# minicopter.net
KiCad netlist of a schematic drawn in EAGLE
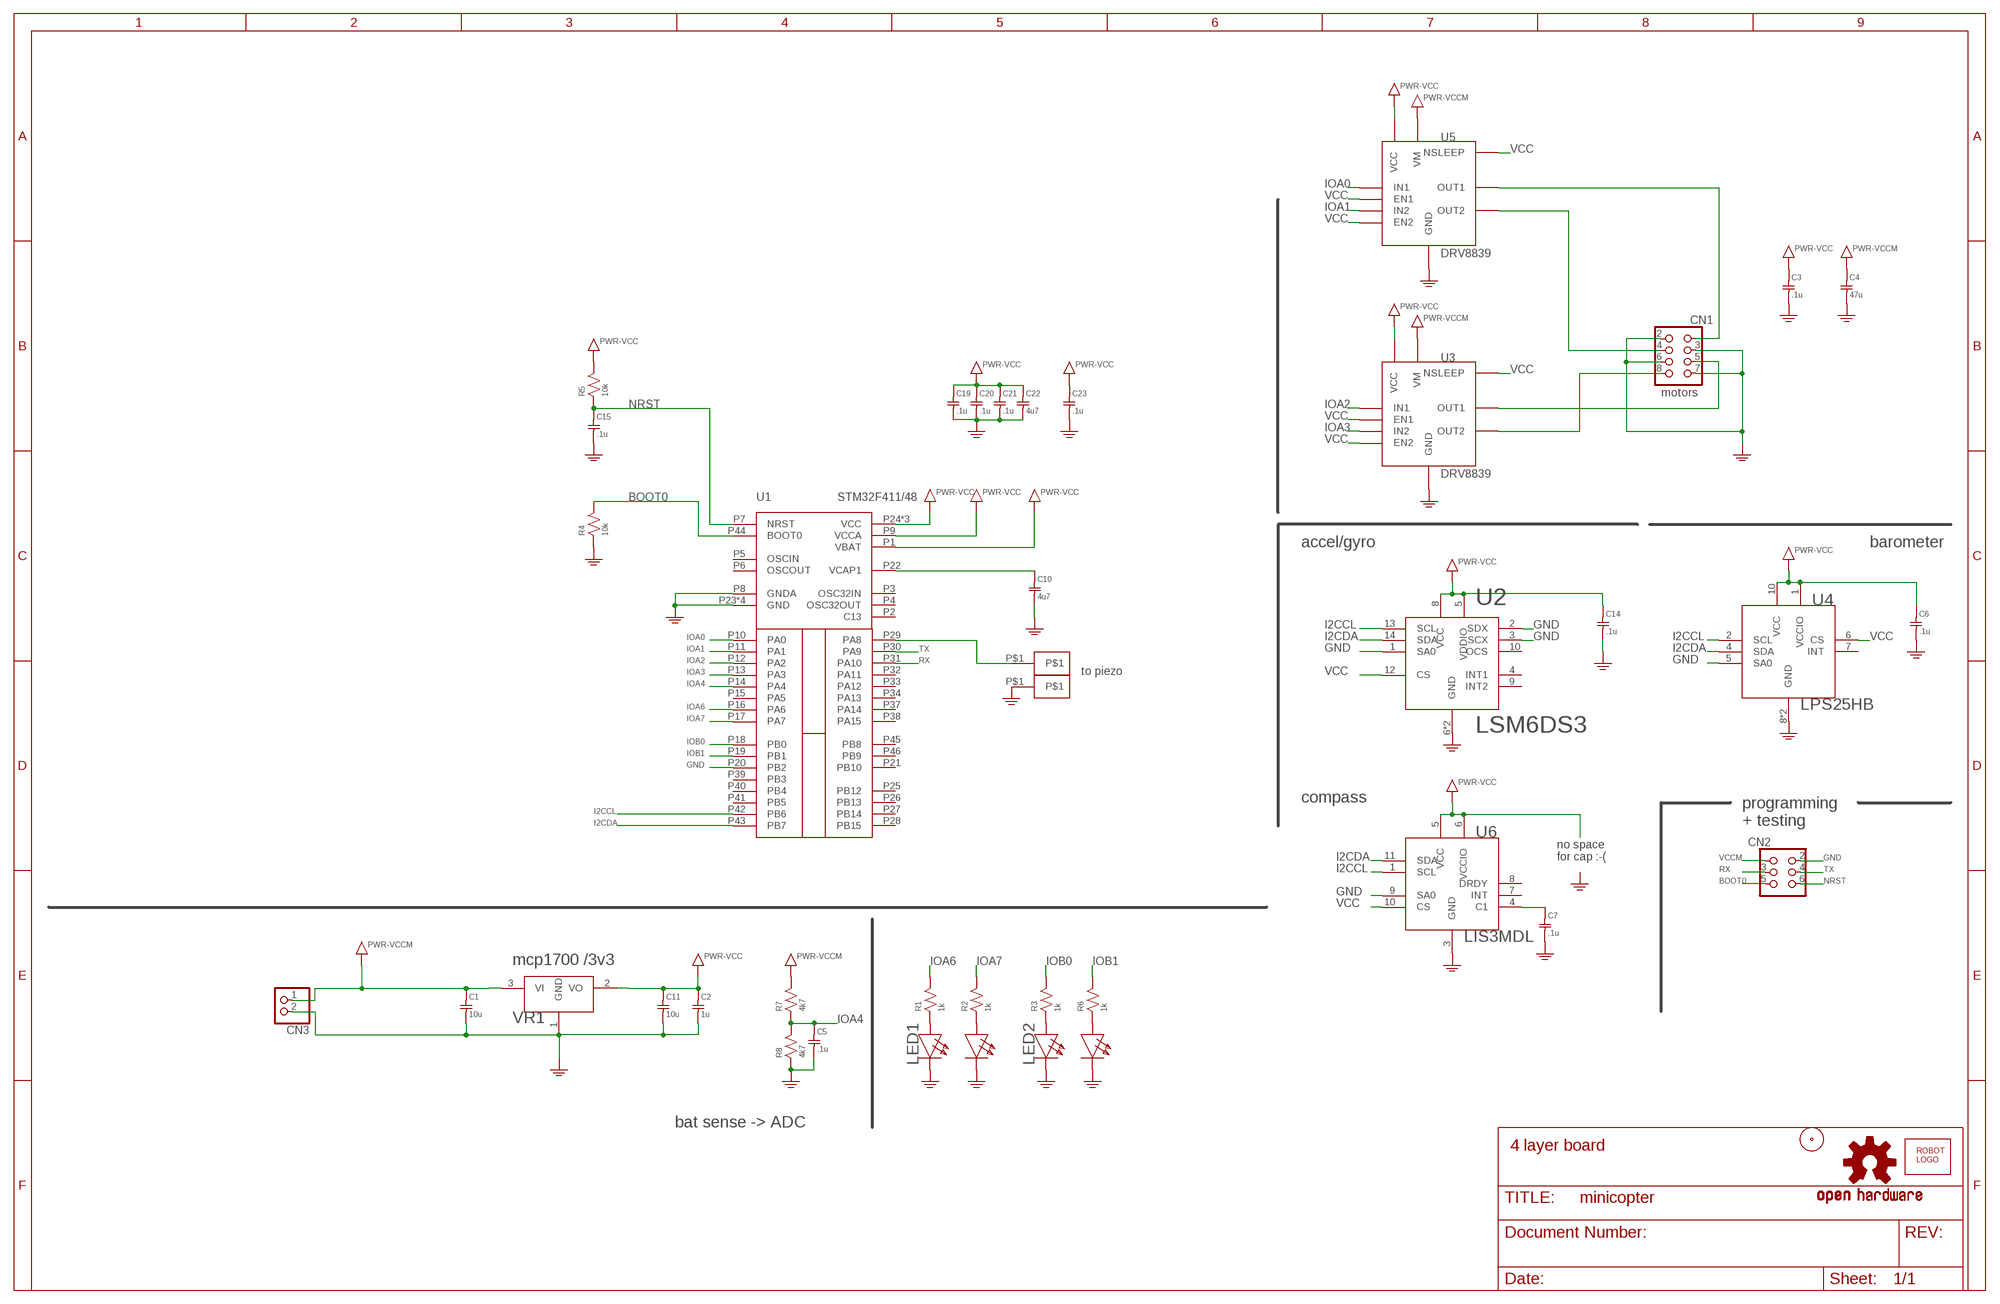
[diagram p0: schematic, sheet 1]

(export (version "E")
  (design (tool "Eeschema 10.0.6"))
  (components
    (comp (ref "C1")
      (value "10u")
      (footprint "eagle-import:SMD0603")
      (libsource (lib "eagle-import") (part "C0603"))
    )
    (comp (ref "C2")
      (value "1u")
      (footprint "eagle-import:SMD0603")
      (libsource (lib "eagle-import") (part "C0603"))
    )
    (comp (ref "C3")
      (value ".1u")
      (footprint "eagle-import:SMD0603")
      (libsource (lib "eagle-import") (part "C0603"))
    )
    (comp (ref "C4")
      (value "47u")
      (footprint "eagle-import:SMD0805")
      (libsource (lib "eagle-import") (part "C0805"))
    )
    (comp (ref "C5")
      (value ".1u")
      (footprint "eagle-import:SMD0603")
      (libsource (lib "eagle-import") (part "C0603"))
    )
    (comp (ref "C6")
      (value ".1u")
      (footprint "eagle-import:SMD0603")
      (libsource (lib "eagle-import") (part "C0603"))
    )
    (comp (ref "C7")
      (value ".1u")
      (footprint "eagle-import:SMD0603")
      (libsource (lib "eagle-import") (part "C0603"))
    )
    (comp (ref "C10")
      (value "4u7")
      (footprint "eagle-import:SMD0603")
      (libsource (lib "eagle-import") (part "C0603"))
    )
    (comp (ref "C11")
      (value "10u")
      (footprint "eagle-import:SMD0603")
      (libsource (lib "eagle-import") (part "C0603"))
    )
    (comp (ref "C14")
      (value ".1u")
      (footprint "eagle-import:SMD0603")
      (libsource (lib "eagle-import") (part "C0603"))
    )
    (comp (ref "C15")
      (value ".1u")
      (footprint "eagle-import:SMD0603")
      (libsource (lib "eagle-import") (part "C0603"))
    )
    (comp (ref "C19")
      (value ".1u")
      (footprint "eagle-import:SMD0603")
      (libsource (lib "eagle-import") (part "C0603"))
    )
    (comp (ref "C20")
      (value ".1u")
      (footprint "eagle-import:SMD0603")
      (libsource (lib "eagle-import") (part "C0603"))
    )
    (comp (ref "C21")
      (value ".1u")
      (footprint "eagle-import:SMD0603")
      (libsource (lib "eagle-import") (part "C0603"))
    )
    (comp (ref "C22")
      (value "4u7")
      (footprint "eagle-import:SMD0603")
      (libsource (lib "eagle-import") (part "C0603"))
    )
    (comp (ref "C23")
      (value ".1u")
      (footprint "eagle-import:SMD0603")
      (libsource (lib "eagle-import") (part "C0603"))
    )
    (comp (ref "CN1")
      (value "HEADER-2X4")
      (footprint "eagle-import:HEADER-2X04-THM")
      (libsource (lib "eagle-import") (part "HEADER-2X4"))
    )
    (comp (ref "CN2")
      (value "HEADER-3X2-PTH")
      (footprint "eagle-import:HEADER-3X2-PTH")
      (libsource (lib "eagle-import") (part "HEADER-3X2-PTH"))
    )
    (comp (ref "CN3")
      (value "JST_2PIN-THM")
      (footprint "eagle-import:JST-PH-2-THM")
      (libsource (lib "eagle-import") (part "JST_2PIN-THM"))
    )
    (comp (ref "CN4")
      (value "HEADER-1X1SMALL")
      (footprint "eagle-import:HEADER-1X1-SMALL")
      (libsource (lib "eagle-import") (part "HEADER-1X1SMALL"))
    )
    (comp (ref "CN5")
      (value "HEADER-1X1SMALL")
      (footprint "eagle-import:HEADER-1X1-SMALL")
      (libsource (lib "eagle-import") (part "HEADER-1X1SMALL"))
    )
    (comp (ref "LED1")
      (value "LED-DUAL0805")
      (footprint "eagle-import:SMD0805-DUAL")
      (libsource (lib "eagle-import") (part "LED-DUAL0805"))
    )
    (comp (ref "LED2")
      (value "LED-DUAL0805")
      (footprint "eagle-import:SMD0805-DUAL")
      (libsource (lib "eagle-import") (part "LED-DUAL0805"))
    )
    (comp (ref "LOGO1")
      (value "OSHW-LOGOM")
      (footprint "eagle-import:OSHW-LOGO-M")
      (libsource (lib "eagle-import") (part "OSHW-LOGOM"))
    )
    (comp (ref "R1")
      (value "1k")
      (footprint "eagle-import:SMD0603")
      (libsource (lib "eagle-import") (part "R0603"))
    )
    (comp (ref "R2")
      (value "1k")
      (footprint "eagle-import:SMD0603")
      (libsource (lib "eagle-import") (part "R0603"))
    )
    (comp (ref "R3")
      (value "1k")
      (footprint "eagle-import:SMD0603")
      (libsource (lib "eagle-import") (part "R0603"))
    )
    (comp (ref "R4")
      (value "10k")
      (footprint "eagle-import:SMD0603")
      (libsource (lib "eagle-import") (part "R0603"))
    )
    (comp (ref "R5")
      (value "10k")
      (footprint "eagle-import:SMD0603")
      (libsource (lib "eagle-import") (part "R0603"))
    )
    (comp (ref "R6")
      (value "1k")
      (footprint "eagle-import:SMD0603")
      (libsource (lib "eagle-import") (part "R0603"))
    )
    (comp (ref "R7")
      (value "4k7")
      (footprint "eagle-import:SMD0603")
      (libsource (lib "eagle-import") (part "R0603"))
    )
    (comp (ref "R8")
      (value "4k7")
      (footprint "eagle-import:SMD0603")
      (libsource (lib "eagle-import") (part "R0603"))
    )
    (comp (ref "U$1")
      (value "ROBOTMAN-LOGO")
      (footprint "eagle-import:ROBOTMAN-LOGO")
      (libsource (lib "eagle-import") (part "ROBOTMAN-LOGO"))
    )
    (comp (ref "U$2")
      (value "FIDUCIAL")
      (footprint "eagle-import:FIDUCIAL")
      (libsource (lib "eagle-import") (part "FIDUCIAL"))
    )
    (comp (ref "U1")
      (value "STM32F411/48")
      (footprint "eagle-import:UQPFN48")
      (libsource (lib "eagle-import") (part "STM32F411/48"))
    )
    (comp (ref "U2")
      (value "LSM6DS3")
      (footprint "eagle-import:LGA14A")
      (libsource (lib "eagle-import") (part "LSM6DS3"))
    )
    (comp (ref "U3")
      (value "DRV8839")
      (footprint "eagle-import:WSON12")
      (libsource (lib "eagle-import") (part "DRV8839"))
    )
    (comp (ref "U4")
      (value "LPS25HB")
      (footprint "eagle-import:HLGA10L")
      (libsource (lib "eagle-import") (part "LPS25HB"))
    )
    (comp (ref "U5")
      (value "DRV8839")
      (footprint "eagle-import:WSON12")
      (libsource (lib "eagle-import") (part "DRV8839"))
    )
    (comp (ref "U6")
      (value "LIS3MDL")
      (footprint "eagle-import:LGA12")
      (libsource (lib "eagle-import") (part "LIS3MDL"))
    )
    (comp (ref "VR1")
      (value "mcp1700 /3v3")
      (footprint "eagle-import:SOT-23-3")
      (libsource (lib "eagle-import") (part "REGULATOR-SOT23-3"))
    )
  )
  (nets
    (net (code "1") (name "/BOOT0") (class "Default")
      (node (ref "CN2") (pin "5") (pinfunction "P$5_5") (pintype "passive"))
      (node (ref "R4") (pin "2") (pinfunction "P$2_2") (pintype "passive"))
      (node (ref "U1") (pin "P44") (pinfunction "BOOT0_P44") (pintype "bidirectional"))
    )
    (net (code "2") (name "/I2CCL") (class "Default")
      (node (ref "U1") (pin "P42") (pinfunction "PB6_P42") (pintype "bidirectional"))
      (node (ref "U2") (pin "13") (pinfunction "SCL_13") (pintype "bidirectional"))
      (node (ref "U4") (pin "2") (pinfunction "SCL_2") (pintype "bidirectional"))
      (node (ref "U6") (pin "1") (pinfunction "SCL_1") (pintype "bidirectional"))
    )
    (net (code "3") (name "/I2CDA") (class "Default")
      (node (ref "U1") (pin "P43") (pinfunction "PB7_P43") (pintype "bidirectional"))
      (node (ref "U2") (pin "14") (pinfunction "SDA_14") (pintype "bidirectional"))
      (node (ref "U4") (pin "4") (pinfunction "SDA_4") (pintype "bidirectional"))
      (node (ref "U6") (pin "11") (pinfunction "SDA_11") (pintype "bidirectional"))
    )
    (net (code "4") (name "/IOA0") (class "Default")
      (node (ref "U1") (pin "P10") (pinfunction "PA0_P10") (pintype "bidirectional"))
      (node (ref "U5") (pin "10") (pinfunction "IN1_10") (pintype "input"))
    )
    (net (code "5") (name "/IOA1") (class "Default")
      (node (ref "U1") (pin "P11") (pinfunction "PA1_P11") (pintype "bidirectional"))
      (node (ref "U5") (pin "8") (pinfunction "IN2_8") (pintype "input"))
    )
    (net (code "6") (name "/IOA2") (class "Default")
      (node (ref "U1") (pin "P12") (pinfunction "PA2_P12") (pintype "bidirectional"))
      (node (ref "U3") (pin "10") (pinfunction "IN1_10") (pintype "input"))
    )
    (net (code "7") (name "/IOA3") (class "Default")
      (node (ref "U1") (pin "P13") (pinfunction "PA3_P13") (pintype "bidirectional"))
      (node (ref "U3") (pin "8") (pinfunction "IN2_8") (pintype "input"))
    )
    (net (code "8") (name "/IOA4") (class "Default")
      (node (ref "C5") (pin "1") (pinfunction "P$1_1") (pintype "passive"))
      (node (ref "R7") (pin "1") (pinfunction "P$1_1") (pintype "passive"))
      (node (ref "R8") (pin "2") (pinfunction "P$2_2") (pintype "passive"))
      (node (ref "U1") (pin "P14") (pinfunction "PA4_P14") (pintype "bidirectional"))
    )
    (net (code "9") (name "/IOA6") (class "Default")
      (node (ref "R1") (pin "2") (pinfunction "P$2_2") (pintype "passive"))
      (node (ref "U1") (pin "P16") (pinfunction "PA6_P16") (pintype "bidirectional"))
    )
    (net (code "10") (name "/IOA7") (class "Default")
      (node (ref "R2") (pin "2") (pinfunction "P$2_2") (pintype "passive"))
      (node (ref "U1") (pin "P17") (pinfunction "PA7_P17") (pintype "bidirectional"))
    )
    (net (code "11") (name "/IOB0") (class "Default")
      (node (ref "R3") (pin "2") (pinfunction "P$2_2") (pintype "passive"))
      (node (ref "U1") (pin "P18") (pinfunction "PB0_P18") (pintype "bidirectional"))
    )
    (net (code "12") (name "/IOB1") (class "Default")
      (node (ref "R6") (pin "2") (pinfunction "P$2_2") (pintype "passive"))
      (node (ref "U1") (pin "P19") (pinfunction "PB1_P19") (pintype "bidirectional"))
    )
    (net (code "13") (name "/NRST") (class "Default")
      (node (ref "C15") (pin "1") (pinfunction "P$1_1") (pintype "passive"))
      (node (ref "CN2") (pin "6") (pinfunction "P$6_6") (pintype "passive"))
      (node (ref "R5") (pin "1") (pinfunction "P$1_1") (pintype "passive"))
      (node (ref "U1") (pin "P7") (pinfunction "NRST_P7") (pintype "bidirectional"))
    )
    (net (code "14") (name "/RX") (class "Default")
      (node (ref "CN2") (pin "3") (pinfunction "P$3_3") (pintype "passive"))
      (node (ref "U1") (pin "P31") (pinfunction "PA10_P31") (pintype "bidirectional"))
    )
    (net (code "15") (name "/TX") (class "Default")
      (node (ref "CN2") (pin "4") (pinfunction "P$4_4") (pintype "passive"))
      (node (ref "U1") (pin "P30") (pinfunction "PA9_P30") (pintype "bidirectional"))
    )
    (net (code "16") (name "Net-(C7-P$1)") (class "Default")
      (node (ref "C7") (pin "1") (pinfunction "P$1_1") (pintype "passive"))
      (node (ref "U6") (pin "4") (pinfunction "C1_4") (pintype "bidirectional"))
    )
    (net (code "17") (name "Net-(C10-P$1)") (class "Default")
      (node (ref "C10") (pin "1") (pinfunction "P$1_1") (pintype "passive"))
      (node (ref "U1") (pin "P22") (pinfunction "VCAP1_P22") (pintype "bidirectional"))
    )
    (net (code "18") (name "Net-(CN1-P$1)") (class "Default")
      (node (ref "CN1") (pin "1") (pinfunction "P$1_1") (pintype "passive"))
      (node (ref "U5") (pin "3") (pinfunction "OUT1_3") (pintype "output"))
    )
    (net (code "19") (name "Net-(CN1-P$4)") (class "Default")
      (node (ref "CN1") (pin "4") (pinfunction "P$4_4") (pintype "passive"))
      (node (ref "U5") (pin "4") (pinfunction "OUT2_4") (pintype "output"))
    )
    (net (code "20") (name "Net-(CN1-P$5)") (class "Default")
      (node (ref "CN1") (pin "5") (pinfunction "P$5_5") (pintype "passive"))
      (node (ref "U3") (pin "3") (pinfunction "OUT1_3") (pintype "output"))
    )
    (net (code "21") (name "Net-(CN1-P$8)") (class "Default")
      (node (ref "CN1") (pin "8") (pinfunction "P$8_8") (pintype "passive"))
      (node (ref "U3") (pin "4") (pinfunction "OUT2_4") (pintype "output"))
    )
    (net (code "22") (name "Net-(LED1-AB)") (class "Default")
      (node (ref "LED1") (pin "1") (pinfunction "AB_1") (pintype "passive"))
      (node (ref "R1") (pin "1") (pinfunction "P$1_1") (pintype "passive"))
    )
    (net (code "23") (name "Net-(LED1-AR)") (class "Default")
      (node (ref "LED1") (pin "4") (pinfunction "AR_4") (pintype "passive"))
      (node (ref "R2") (pin "1") (pinfunction "P$1_1") (pintype "passive"))
    )
    (net (code "24") (name "Net-(LED2-AB)") (class "Default")
      (node (ref "LED2") (pin "1") (pinfunction "AB_1") (pintype "passive"))
      (node (ref "R3") (pin "1") (pinfunction "P$1_1") (pintype "passive"))
    )
    (net (code "25") (name "Net-(LED2-AR)") (class "Default")
      (node (ref "LED2") (pin "4") (pinfunction "AR_4") (pintype "passive"))
      (node (ref "R6") (pin "1") (pinfunction "P$1_1") (pintype "passive"))
    )
    (net (code "26") (name "Net-(U1-PA8)") (class "Default")
      (node (ref "CN4") (pin "P$1") (pinfunction "P$1_P$1") (pintype "bidirectional"))
      (node (ref "U1") (pin "P29") (pinfunction "PA8_P29") (pintype "bidirectional"))
    )
    (net (code "27") (name "PWR-GND") (class "Default")
      (node (ref "C1") (pin "2") (pinfunction "P$2_2") (pintype "passive"))
      (node (ref "C10") (pin "2") (pinfunction "P$2_2") (pintype "passive"))
      (node (ref "C11") (pin "2") (pinfunction "P$2_2") (pintype "passive"))
      (node (ref "C14") (pin "2") (pinfunction "P$2_2") (pintype "passive"))
      (node (ref "C15") (pin "2") (pinfunction "P$2_2") (pintype "passive"))
      (node (ref "C19") (pin "2") (pinfunction "P$2_2") (pintype "passive"))
      (node (ref "C2") (pin "2") (pinfunction "P$2_2") (pintype "passive"))
      (node (ref "C20") (pin "2") (pinfunction "P$2_2") (pintype "passive"))
      (node (ref "C21") (pin "2") (pinfunction "P$2_2") (pintype "passive"))
      (node (ref "C22") (pin "2") (pinfunction "P$2_2") (pintype "passive"))
      (node (ref "C23") (pin "2") (pinfunction "P$2_2") (pintype "passive"))
      (node (ref "C3") (pin "2") (pinfunction "P$2_2") (pintype "passive"))
      (node (ref "C4") (pin "2") (pinfunction "P$2_2") (pintype "passive"))
      (node (ref "C5") (pin "2") (pinfunction "P$2_2") (pintype "passive"))
      (node (ref "C6") (pin "2") (pinfunction "P$2_2") (pintype "passive"))
      (node (ref "C7") (pin "2") (pinfunction "P$2_2") (pintype "passive"))
      (node (ref "CN1") (pin "2") (pinfunction "P$2_2") (pintype "passive"))
      (node (ref "CN1") (pin "3") (pinfunction "P$3_3") (pintype "passive"))
      (node (ref "CN1") (pin "6") (pinfunction "P$6_6") (pintype "passive"))
      (node (ref "CN1") (pin "7") (pinfunction "P$7_7") (pintype "passive"))
      (node (ref "CN2") (pin "2") (pinfunction "P$2_2") (pintype "passive"))
      (node (ref "CN3") (pin "2") (pinfunction "1_2") (pintype "passive"))
      (node (ref "CN5") (pin "P$1") (pinfunction "P$1_P$1") (pintype "bidirectional"))
      (node (ref "LED1") (pin "2") (pinfunction "CB_2") (pintype "passive"))
      (node (ref "LED1") (pin "3") (pinfunction "CR_3") (pintype "passive"))
      (node (ref "LED2") (pin "2") (pinfunction "CB_2") (pintype "passive"))
      (node (ref "LED2") (pin "3") (pinfunction "CR_3") (pintype "passive"))
      (node (ref "R4") (pin "1") (pinfunction "P$1_1") (pintype "passive"))
      (node (ref "R8") (pin "1") (pinfunction "P$1_1") (pintype "passive"))
      (node (ref "U1") (pin "P20") (pinfunction "PB2_P20") (pintype "bidirectional"))
      (node (ref "U1") (pin "P23") (pinfunction "GND_P23") (pintype "bidirectional"))
      (node (ref "U1") (pin "P35") (pinfunction "GND_P35") (pintype "bidirectional"))
      (node (ref "U1") (pin "P47") (pinfunction "GND_P47") (pintype "bidirectional"))
      (node (ref "U1") (pin "P8") (pinfunction "GNDA_P8") (pintype "bidirectional"))
      (node (ref "U1") (pin "PAD") (pinfunction "GND_PAD") (pintype "bidirectional"))
      (node (ref "U2") (pin "1") (pinfunction "SA0_1") (pintype "bidirectional"))
      (node (ref "U2") (pin "2") (pinfunction "SDX_2") (pintype "bidirectional"))
      (node (ref "U2") (pin "3") (pinfunction "SCX_3") (pintype "bidirectional"))
      (node (ref "U2") (pin "6") (pinfunction "GND_6") (pintype "power_in"))
      (node (ref "U2") (pin "7") (pinfunction "GND_7") (pintype "power_in"))
      (node (ref "U3") (pin "5") (pinfunction "GND_5") (pintype "bidirectional"))
      (node (ref "U3") (pin "6") (pinfunction "GND_6") (pintype "bidirectional"))
      (node (ref "U3") (pin "GND3") (pinfunction "GND_GND3") (pintype "bidirectional"))
      (node (ref "U3") (pin "GND4") (pinfunction "GND_GND4") (pintype "bidirectional"))
      (node (ref "U3") (pin "GND5") (pinfunction "GND_GND5") (pintype "bidirectional"))
      (node (ref "U3") (pin "GND6") (pinfunction "GND_GND6") (pintype "bidirectional"))
      (node (ref "U3") (pin "GND7") (pinfunction "GND_GND7") (pintype "bidirectional"))
      (node (ref "U4") (pin "5") (pinfunction "SA0_5") (pintype "bidirectional"))
      (node (ref "U4") (pin "8") (pinfunction "GND_8") (pintype "bidirectional"))
      (node (ref "U4") (pin "9") (pinfunction "GND_9") (pintype "bidirectional"))
      (node (ref "U5") (pin "5") (pinfunction "GND_5") (pintype "bidirectional"))
      (node (ref "U5") (pin "6") (pinfunction "GND_6") (pintype "bidirectional"))
      (node (ref "U5") (pin "GND3") (pinfunction "GND_GND3") (pintype "bidirectional"))
      (node (ref "U5") (pin "GND4") (pinfunction "GND_GND4") (pintype "bidirectional"))
      (node (ref "U5") (pin "GND5") (pinfunction "GND_GND5") (pintype "bidirectional"))
      (node (ref "U5") (pin "GND6") (pinfunction "GND_GND6") (pintype "bidirectional"))
      (node (ref "U5") (pin "GND7") (pinfunction "GND_GND7") (pintype "bidirectional"))
      (node (ref "U6") (pin "3") (pinfunction "GND_3") (pintype "bidirectional"))
      (node (ref "U6") (pin "9") (pinfunction "SA0_9") (pintype "bidirectional"))
      (node (ref "VR1") (pin "1") (pinfunction "GND_1") (pintype "bidirectional"))
    )
    (net (code "28") (name "PWR-VCC") (class "Default")
      (node (ref "C11") (pin "1") (pinfunction "P$1_1") (pintype "passive"))
      (node (ref "C14") (pin "1") (pinfunction "P$1_1") (pintype "passive"))
      (node (ref "C19") (pin "1") (pinfunction "P$1_1") (pintype "passive"))
      (node (ref "C2") (pin "1") (pinfunction "P$1_1") (pintype "passive"))
      (node (ref "C20") (pin "1") (pinfunction "P$1_1") (pintype "passive"))
      (node (ref "C21") (pin "1") (pinfunction "P$1_1") (pintype "passive"))
      (node (ref "C22") (pin "1") (pinfunction "P$1_1") (pintype "passive"))
      (node (ref "C23") (pin "1") (pinfunction "P$1_1") (pintype "passive"))
      (node (ref "C3") (pin "1") (pinfunction "P$1_1") (pintype "passive"))
      (node (ref "C6") (pin "1") (pinfunction "P$1_1") (pintype "passive"))
      (node (ref "R5") (pin "2") (pinfunction "P$2_2") (pintype "passive"))
      (node (ref "U1") (pin "P1") (pinfunction "VBAT_P1") (pintype "bidirectional"))
      (node (ref "U1") (pin "P24") (pinfunction "VCC_P24") (pintype "bidirectional"))
      (node (ref "U1") (pin "P36") (pinfunction "VCC_P36") (pintype "bidirectional"))
      (node (ref "U1") (pin "P48") (pinfunction "VCC_P48") (pintype "bidirectional"))
      (node (ref "U1") (pin "P9") (pinfunction "VCCA_P9") (pintype "bidirectional"))
      (node (ref "U2") (pin "12") (pinfunction "CS_12") (pintype "bidirectional"))
      (node (ref "U2") (pin "5") (pinfunction "VDDIO_5") (pintype "bidirectional"))
      (node (ref "U2") (pin "8") (pinfunction "VCC_8") (pintype "power_in"))
      (node (ref "U3") (pin "11") (pinfunction "NSLEEP_11") (pintype "input"))
      (node (ref "U3") (pin "12") (pinfunction "VCC_12") (pintype "bidirectional"))
      (node (ref "U3") (pin "7") (pinfunction "EN2_7") (pintype "input"))
      (node (ref "U3") (pin "9") (pinfunction "EN1_9") (pintype "input"))
      (node (ref "U4") (pin "1") (pinfunction "VCCIO_1") (pintype "bidirectional"))
      (node (ref "U4") (pin "10") (pinfunction "VCC_10") (pintype "bidirectional"))
      (node (ref "U4") (pin "6") (pinfunction "CS_6") (pintype "bidirectional"))
      (node (ref "U5") (pin "11") (pinfunction "NSLEEP_11") (pintype "input"))
      (node (ref "U5") (pin "12") (pinfunction "VCC_12") (pintype "bidirectional"))
      (node (ref "U5") (pin "7") (pinfunction "EN2_7") (pintype "input"))
      (node (ref "U5") (pin "9") (pinfunction "EN1_9") (pintype "input"))
      (node (ref "U6") (pin "10") (pinfunction "CS_10") (pintype "bidirectional"))
      (node (ref "U6") (pin "5") (pinfunction "VCC_5") (pintype "bidirectional"))
      (node (ref "U6") (pin "6") (pinfunction "VCCIO_6") (pintype "bidirectional"))
      (node (ref "VR1") (pin "2") (pinfunction "VO_2") (pintype "bidirectional"))
    )
    (net (code "29") (name "PWR-VCCM") (class "Default")
      (node (ref "C1") (pin "1") (pinfunction "P$1_1") (pintype "passive"))
      (node (ref "C4") (pin "1") (pinfunction "P$1_1") (pintype "passive"))
      (node (ref "CN2") (pin "1") (pinfunction "P$1_1") (pintype "passive"))
      (node (ref "CN3") (pin "1") (pinfunction "2_1") (pintype "passive"))
      (node (ref "R7") (pin "2") (pinfunction "P$2_2") (pintype "passive"))
      (node (ref "U3") (pin "1") (pinfunction "VM_1") (pintype "bidirectional"))
      (node (ref "U3") (pin "2") (pinfunction "VM_2") (pintype "bidirectional"))
      (node (ref "U5") (pin "1") (pinfunction "VM_1") (pintype "bidirectional"))
      (node (ref "U5") (pin "2") (pinfunction "VM_2") (pintype "bidirectional"))
      (node (ref "VR1") (pin "3") (pinfunction "VI_3") (pintype "bidirectional"))
    )
    (net (code "30") (name "unconnected-(U1-C13-PadP2)") (class "Default")
      (node (ref "U1") (pin "P2") (pinfunction "C13_P2") (pintype "bidirectional"))
    )
    (net (code "31") (name "unconnected-(U1-OSC32IN-PadP3)") (class "Default")
      (node (ref "U1") (pin "P3") (pinfunction "OSC32IN_P3") (pintype "bidirectional"))
    )
    (net (code "32") (name "unconnected-(U1-OSC32OUT-PadP4)") (class "Default")
      (node (ref "U1") (pin "P4") (pinfunction "OSC32OUT_P4") (pintype "bidirectional"))
    )
    (net (code "33") (name "unconnected-(U1-OSCIN-PadP5)") (class "Default")
      (node (ref "U1") (pin "P5") (pinfunction "OSCIN_P5") (pintype "bidirectional"))
    )
    (net (code "34") (name "unconnected-(U1-OSCOUT-PadP6)") (class "Default")
      (node (ref "U1") (pin "P6") (pinfunction "OSCOUT_P6") (pintype "bidirectional"))
    )
    (net (code "35") (name "unconnected-(U1-PA5-PadP15)") (class "Default")
      (node (ref "U1") (pin "P15") (pinfunction "PA5_P15") (pintype "bidirectional"))
    )
    (net (code "36") (name "unconnected-(U1-PA11-PadP32)") (class "Default")
      (node (ref "U1") (pin "P32") (pinfunction "PA11_P32") (pintype "bidirectional"))
    )
    (net (code "37") (name "unconnected-(U1-PA12-PadP33)") (class "Default")
      (node (ref "U1") (pin "P33") (pinfunction "PA12_P33") (pintype "bidirectional"))
    )
    (net (code "38") (name "unconnected-(U1-PA13-PadP34)") (class "Default")
      (node (ref "U1") (pin "P34") (pinfunction "PA13_P34") (pintype "bidirectional"))
    )
    (net (code "39") (name "unconnected-(U1-PA14-PadP37)") (class "Default")
      (node (ref "U1") (pin "P37") (pinfunction "PA14_P37") (pintype "bidirectional"))
    )
    (net (code "40") (name "unconnected-(U1-PA15-PadP38)") (class "Default")
      (node (ref "U1") (pin "P38") (pinfunction "PA15_P38") (pintype "bidirectional"))
    )
    (net (code "41") (name "unconnected-(U1-PB3-PadP39)") (class "Default")
      (node (ref "U1") (pin "P39") (pinfunction "PB3_P39") (pintype "bidirectional"))
    )
    (net (code "42") (name "unconnected-(U1-PB4-PadP40)") (class "Default")
      (node (ref "U1") (pin "P40") (pinfunction "PB4_P40") (pintype "bidirectional"))
    )
    (net (code "43") (name "unconnected-(U1-PB5-PadP41)") (class "Default")
      (node (ref "U1") (pin "P41") (pinfunction "PB5_P41") (pintype "bidirectional"))
    )
    (net (code "44") (name "unconnected-(U1-PB8-PadP45)") (class "Default")
      (node (ref "U1") (pin "P45") (pinfunction "PB8_P45") (pintype "bidirectional"))
    )
    (net (code "45") (name "unconnected-(U1-PB9-PadP46)") (class "Default")
      (node (ref "U1") (pin "P46") (pinfunction "PB9_P46") (pintype "bidirectional"))
    )
    (net (code "46") (name "unconnected-(U1-PB10-PadP21)") (class "Default")
      (node (ref "U1") (pin "P21") (pinfunction "PB10_P21") (pintype "bidirectional"))
    )
    (net (code "47") (name "unconnected-(U1-PB12-PadP25)") (class "Default")
      (node (ref "U1") (pin "P25") (pinfunction "PB12_P25") (pintype "bidirectional"))
    )
    (net (code "48") (name "unconnected-(U1-PB13-PadP26)") (class "Default")
      (node (ref "U1") (pin "P26") (pinfunction "PB13_P26") (pintype "bidirectional"))
    )
    (net (code "49") (name "unconnected-(U1-PB14-PadP27)") (class "Default")
      (node (ref "U1") (pin "P27") (pinfunction "PB14_P27") (pintype "bidirectional"))
    )
    (net (code "50") (name "unconnected-(U1-PB15-PadP28)") (class "Default")
      (node (ref "U1") (pin "P28") (pinfunction "PB15_P28") (pintype "bidirectional"))
    )
    (net (code "51") (name "unconnected-(U2-INT1-Pad4)") (class "Default")
      (node (ref "U2") (pin "4") (pinfunction "INT1_4") (pintype "bidirectional"))
    )
    (net (code "52") (name "unconnected-(U2-INT2-Pad9)") (class "Default")
      (node (ref "U2") (pin "9") (pinfunction "INT2_9") (pintype "bidirectional"))
    )
    (net (code "53") (name "unconnected-(U2-OCS-Pad10)") (class "Default")
      (node (ref "U2") (pin "10") (pinfunction "OCS_10") (pintype "bidirectional"))
    )
    (net (code "54") (name "unconnected-(U4-INT-Pad7)") (class "Default")
      (node (ref "U4") (pin "7") (pinfunction "INT_7") (pintype "bidirectional"))
    )
    (net (code "55") (name "unconnected-(U6-DRDY-Pad8)") (class "Default")
      (node (ref "U6") (pin "8") (pinfunction "DRDY_8") (pintype "bidirectional"))
    )
    (net (code "56") (name "unconnected-(U6-INT-Pad7)") (class "Default")
      (node (ref "U6") (pin "7") (pinfunction "INT_7") (pintype "bidirectional"))
    )
  )
)
